# mcu.net
KiCad netlist of a schematic drawn in Altium Designer
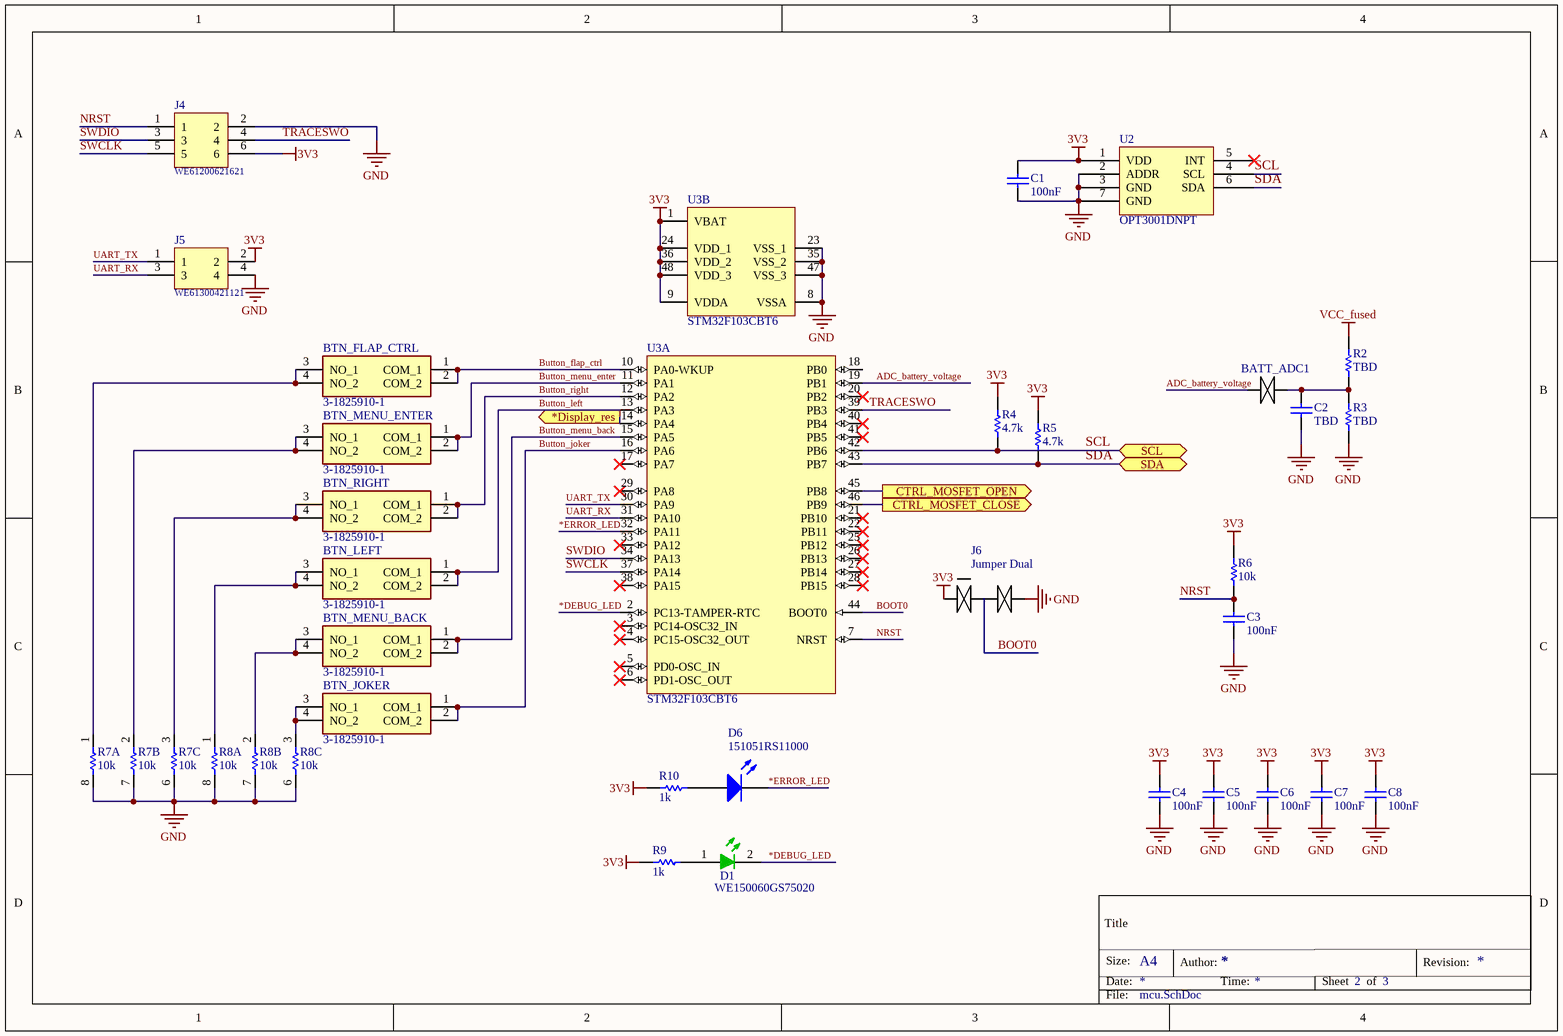
[diagram p0: mcu.SchDoc]

(export (version "E")
  (design (tool "Eeschema 10.0.6"))
  (components
    (comp (ref "BATT_ADC1")
      (value "TIMER")
      (footprint "JUMPER_SINGLE_SMALL")
      (description "2 pads which can be connected truth soldering")
      (libsource (lib "connectors") (part "JUMPER_SINGLE"))
    )
    (comp (ref "BTN_FLAP_CTRL")
      (value "3-1825910-1")
      (footprint "318259101")
      (description "Switch")
      (libsource (lib "Schlib") (part "3-1825910-1"))
    )
    (comp (ref "BTN_JOKER")
      (value "3-1825910-1")
      (footprint "318259101")
      (description "Switch")
      (libsource (lib "Schlib") (part "3-1825910-1"))
    )
    (comp (ref "BTN_LEFT")
      (value "3-1825910-1")
      (footprint "318259101")
      (description "Switch")
      (libsource (lib "Schlib") (part "3-1825910-1"))
    )
    (comp (ref "BTN_MENU_BACK")
      (value "3-1825910-1")
      (footprint "318259101")
      (description "Switch")
      (libsource (lib "Schlib") (part "3-1825910-1"))
    )
    (comp (ref "BTN_MENU_ENTER")
      (value "3-1825910-1")
      (footprint "318259101")
      (description "Switch")
      (libsource (lib "Schlib") (part "3-1825910-1"))
    )
    (comp (ref "BTN_RIGHT")
      (value "3-1825910-1")
      (footprint "318259101")
      (description "Switch")
      (libsource (lib "Schlib") (part "3-1825910-1"))
    )
    (comp (ref "C1")
      (value "100nF")
      (footprint "CAP0603")
      (description "Chip Capacitor 0603, Body 1.6x0.8mm, IPC Medium Density")
      (libsource (lib "capacitors") (part "Capacitor 0603"))
    )
    (comp (ref "C2")
      (value "TBD")
      (footprint "CAP0603")
      (description "Chip Capacitor 0603, Body 1.6x0.8mm, IPC Medium Density")
      (libsource (lib "capacitors") (part "Capacitor 0603"))
    )
    (comp (ref "C3")
      (value "100nF")
      (footprint "CAP0603")
      (description "Chip Capacitor 0603, Body 1.6x0.8mm, IPC Medium Density")
      (libsource (lib "capacitors") (part "Capacitor 0603"))
    )
    (comp (ref "C4")
      (value "100nF")
      (footprint "CAP0603")
      (description "Chip Capacitor 0603, Body 1.6x0.8mm, IPC Medium Density")
      (libsource (lib "capacitors") (part "Capacitor 0603"))
    )
    (comp (ref "C5")
      (value "100nF")
      (footprint "CAP0603")
      (description "Chip Capacitor 0603, Body 1.6x0.8mm, IPC Medium Density")
      (libsource (lib "capacitors") (part "Capacitor 0603"))
    )
    (comp (ref "C6")
      (value "100nF")
      (footprint "CAP0603")
      (description "Chip Capacitor 0603, Body 1.6x0.8mm, IPC Medium Density")
      (libsource (lib "capacitors") (part "Capacitor 0603"))
    )
    (comp (ref "C7")
      (value "100nF")
      (footprint "CAP0603")
      (description "Chip Capacitor 0603, Body 1.6x0.8mm, IPC Medium Density")
      (libsource (lib "capacitors") (part "Capacitor 0603"))
    )
    (comp (ref "C8")
      (value "100nF")
      (footprint "CAP0603")
      (description "Chip Capacitor 0603, Body 1.6x0.8mm, IPC Medium Density")
      (libsource (lib "capacitors") (part "Capacitor 0603"))
    )
    (comp (ref "D1")
      (value "WE150060GS75020")
      (footprint "0603 LED Green")
      (description "LED, SMT, 0603(1608), 1.1mm thickness, Green")
      (libsource (lib "diodes") (part "LED Green 0603"))
    )
    (comp (ref "D6")
      (value "151051RS11000")
      (footprint "Type 5mm")
      (description "THT LED round mono-color color lens, WL-TMRW, Red")
      (fields (field (name "MANUFACTURER") "Wuerth Elektronik"))
      (libsource (lib "Altium Content Vault") (part "WE-LED_K1A2-2"))
    )
    (comp (ref "J4")
      (value "WE61200621621")
      (footprint "WE61200621621")
      (description "WR-PHD Box Header, THT, pitch 2.54mm, Dual Row, Vertical, 6pin")
      (fields (field (name "PART NUMBER") "61300621121") (field (name "PUBLISHER") "Wurth Elektronik"))
      (libsource (lib "connectors") (part "WE61200621621"))
    )
    (comp (ref "J5")
      (value "WE61300421121")
      (footprint "WE61300421121")
      (description "WR-PHD Pin Header, THT, pitch 2.54mm, Dual Row, Vertical, 4pin")
      (fields (field (name "PART NUMBER") "61300421121") (field (name "PUBLISHER") "Wurth Elektronik"))
      (libsource (lib "connectors") (part "WE61300421121"))
    )
    (comp (ref "J6")
      (value "Jumper Dual")
      (footprint "Jumper Dual")
      (libsource (lib "miscellaneous") (part "Jumper Dual"))
    )
    (comp (ref "R2")
      (value "TBD")
      (footprint "RES0603")
      (description "Chip Resistor 0603, Body 1.6x0.8mm, IPC Medium Density")
      (libsource (lib "resistors") (part "Resistor 0603"))
    )
    (comp (ref "R3")
      (value "TBD")
      (footprint "RES0603")
      (description "Chip Resistor 0603, Body 1.6x0.8mm, IPC Medium Density")
      (libsource (lib "resistors") (part "Resistor 0603"))
    )
    (comp (ref "R4")
      (value "4.7k")
      (footprint "RES0603")
      (description "Chip Resistor 0603, Body 1.6x0.8mm, IPC Medium Density")
      (libsource (lib "resistors") (part "Resistor 0603"))
    )
    (comp (ref "R5")
      (value "4.7k")
      (footprint "RES0603")
      (description "Chip Resistor 0603, Body 1.6x0.8mm, IPC Medium Density")
      (libsource (lib "resistors") (part "Resistor 0603"))
    )
    (comp (ref "R6")
      (value "10k")
      (footprint "RES0603")
      (description "Chip Resistor 0603, Body 1.0x0.5mm, IPC Medium Density")
      (libsource (lib "resistors") (part "Resistor 0603"))
    )
    (comp (ref "R7")
      (value "10k")
      (footprint "BOUR-CAT16-103J4LF_M")
      (description "10k Array in Alternative symbol")
      (fields (field (name "Comment") "CAT16-103J4LF"))
      (libsource (lib "resistors") (part "CAT16-103J4LF alternative"))
    )
    (comp (ref "R8")
      (value "10k")
      (footprint "BOUR-CAT16-103J4LF_M")
      (description "10k Array in Alternative symbol")
      (fields (field (name "Comment") "CAT16-103J4LF"))
      (libsource (lib "resistors") (part "CAT16-103J4LF alternative"))
    )
    (comp (ref "R9")
      (value "1k")
      (footprint "RES0603")
      (description "Chip Resistor 0603, Body 1.6x0.8mm, IPC Medium Density")
      (libsource (lib "resistors") (part "Resistor 0603"))
    )
    (comp (ref "R10")
      (value "1k")
      (footprint "RES0603")
      (description "Chip Resistor 0603, Body 1.6x0.8mm, IPC Medium Density")
      (libsource (lib "resistors") (part "Resistor 0603"))
    )
    (comp (ref "U2")
      (value "OPT3001DNPT")
      (footprint "OPT3001DNPT")
      (description "Sensoren für Umgebungslicht Ambient Light Sensor -USON -40 to 85")
      (libsource (lib "ic_sensors") (part "OPT3001DNPT"))
    )
    (comp (ref "U3")
      (value "STM32F103CBT6")
      (footprint "STM-LQFP48_M")
      (fields (field (name "PARTNUMBER") "STM32F103C8T6"))
      (libsource (lib "ic_processors") (part "STM32F103CBT6"))
    )
  )
  (nets
    (net (code "1") (name "/*DEBUG_LED") (class "Default")
      (node (ref "D1") (pin "2") (pinfunction "K_2") (pintype "passive"))
      (node (ref "U3") (pin "2") (pinfunction "PC13-TAMPER-RTC_2") (pintype "bidirectional"))
    )
    (net (code "2") (name "/*Display_res") (class "Default")
      (node (ref "U3") (pin "14") (pinfunction "PA4_14") (pintype "bidirectional"))
    )
    (net (code "3") (name "/*ERROR_LED") (class "Default")
      (node (ref "D6") (pin "1") (pinfunction "K_1") (pintype "passive"))
      (node (ref "U3") (pin "32") (pinfunction "PA11_32") (pintype "bidirectional"))
    )
    (net (code "4") (name "/ADC_battery_voltage") (class "Default")
      (node (ref "BATT_ADC1") (pin "2") (pinfunction "B_2") (pintype "passive"))
      (node (ref "U3") (pin "19") (pinfunction "PB1_19") (pintype "bidirectional"))
    )
    (net (code "5") (name "/BOOT0") (class "Default")
      (node (ref "J6") (pin "3") (pinfunction "C_3") (pintype "passive"))
      (node (ref "U3") (pin "44") (pinfunction "BOOT0_44") (pintype "input"))
    )
    (net (code "6") (name "/Button_flap_ctrl") (class "Default")
      (node (ref "BTN_FLAP_CTRL") (pin "1") (pinfunction "COM_1_1") (pintype "passive"))
      (node (ref "BTN_FLAP_CTRL") (pin "2") (pinfunction "COM_2_2") (pintype "passive"))
      (node (ref "U3") (pin "10") (pinfunction "PA0-WKUP_10") (pintype "bidirectional"))
    )
    (net (code "7") (name "/Button_joker") (class "Default")
      (node (ref "BTN_JOKER") (pin "1") (pinfunction "COM_1_1") (pintype "passive"))
      (node (ref "BTN_JOKER") (pin "2") (pinfunction "COM_2_2") (pintype "passive"))
      (node (ref "U3") (pin "16") (pinfunction "PA6_16") (pintype "bidirectional"))
    )
    (net (code "8") (name "/Button_left") (class "Default")
      (node (ref "BTN_LEFT") (pin "1") (pinfunction "COM_1_1") (pintype "passive"))
      (node (ref "BTN_LEFT") (pin "2") (pinfunction "COM_2_2") (pintype "passive"))
      (node (ref "U3") (pin "13") (pinfunction "PA3_13") (pintype "bidirectional"))
    )
    (net (code "9") (name "/Button_menu_back") (class "Default")
      (node (ref "BTN_MENU_BACK") (pin "1") (pinfunction "COM_1_1") (pintype "passive"))
      (node (ref "BTN_MENU_BACK") (pin "2") (pinfunction "COM_2_2") (pintype "passive"))
      (node (ref "U3") (pin "15") (pinfunction "PA5_15") (pintype "bidirectional"))
    )
    (net (code "10") (name "/Button_menu_enter") (class "Default")
      (node (ref "BTN_MENU_ENTER") (pin "1") (pinfunction "COM_1_1") (pintype "passive"))
      (node (ref "BTN_MENU_ENTER") (pin "2") (pinfunction "COM_2_2") (pintype "passive"))
      (node (ref "U3") (pin "11") (pinfunction "PA1_11") (pintype "bidirectional"))
    )
    (net (code "11") (name "/Button_right") (class "Default")
      (node (ref "BTN_RIGHT") (pin "1") (pinfunction "COM_1_1") (pintype "passive"))
      (node (ref "BTN_RIGHT") (pin "2") (pinfunction "COM_2_2") (pintype "passive"))
      (node (ref "U3") (pin "12") (pinfunction "PA2_12") (pintype "bidirectional"))
    )
    (net (code "12") (name "/CTRL_MOSFET_CLOSE") (class "Default")
      (node (ref "U3") (pin "46") (pinfunction "PB9_46") (pintype "bidirectional"))
    )
    (net (code "13") (name "/CTRL_MOSFET_OPEN") (class "Default")
      (node (ref "U3") (pin "45") (pinfunction "PB8_45") (pintype "bidirectional"))
    )
    (net (code "14") (name "/NRST") (class "Default")
      (node (ref "C3") (pin "2") (pinfunction "2_2") (pintype "passive"))
      (node (ref "J4") (pin "1") (pinfunction "1_1") (pintype "power_in"))
      (node (ref "R6") (pin "1") (pinfunction "1_1") (pintype "passive"))
      (node (ref "U3") (pin "7") (pinfunction "NRST_7") (pintype "bidirectional"))
    )
    (net (code "15") (name "/SCL") (class "Default")
      (node (ref "R4") (pin "1") (pinfunction "1_1") (pintype "passive"))
      (node (ref "U2") (pin "4") (pinfunction "SCL_4") (pintype "passive"))
      (node (ref "U3") (pin "42") (pinfunction "PB6_42") (pintype "bidirectional"))
    )
    (net (code "16") (name "/SDA") (class "Default")
      (node (ref "R5") (pin "1") (pinfunction "1_1") (pintype "passive"))
      (node (ref "U2") (pin "6") (pinfunction "SDA_6") (pintype "passive"))
      (node (ref "U3") (pin "43") (pinfunction "PB7_43") (pintype "bidirectional"))
    )
    (net (code "17") (name "/SWCLK") (class "Default")
      (node (ref "J4") (pin "5") (pinfunction "5_5") (pintype "power_in"))
      (node (ref "U3") (pin "37") (pinfunction "PA14_37") (pintype "bidirectional"))
    )
    (net (code "18") (name "/SWDIO") (class "Default")
      (node (ref "J4") (pin "3") (pinfunction "3_3") (pintype "power_in"))
      (node (ref "U3") (pin "34") (pinfunction "PA13_34") (pintype "bidirectional"))
    )
    (net (code "19") (name "/TRACESWO") (class "Default")
      (node (ref "J4") (pin "4") (pinfunction "4_4") (pintype "power_in"))
      (node (ref "U3") (pin "39") (pinfunction "PB3_39") (pintype "bidirectional"))
    )
    (net (code "20") (name "/UART_RX") (class "Default")
      (node (ref "J5") (pin "3") (pinfunction "3_3") (pintype "power_in"))
      (node (ref "U3") (pin "31") (pinfunction "PA10_31") (pintype "bidirectional"))
    )
    (net (code "21") (name "/UART_TX") (class "Default")
      (node (ref "J5") (pin "1") (pinfunction "1_1") (pintype "power_in"))
      (node (ref "U3") (pin "30") (pinfunction "PA9_30") (pintype "bidirectional"))
    )
    (net (code "22") (name "3V3") (class "Default")
      (node (ref "C1") (pin "2") (pinfunction "2_2") (pintype "passive"))
      (node (ref "C4") (pin "2") (pinfunction "2_2") (pintype "passive"))
      (node (ref "C5") (pin "2") (pinfunction "2_2") (pintype "passive"))
      (node (ref "C6") (pin "2") (pinfunction "2_2") (pintype "passive"))
      (node (ref "C7") (pin "2") (pinfunction "2_2") (pintype "passive"))
      (node (ref "C8") (pin "2") (pinfunction "2_2") (pintype "passive"))
      (node (ref "J4") (pin "6") (pinfunction "6_6") (pintype "power_in"))
      (node (ref "J5") (pin "2") (pinfunction "2_2") (pintype "power_in"))
      (node (ref "J6") (pin "1") (pinfunction "A_1") (pintype "passive"))
      (node (ref "R10") (pin "2") (pinfunction "2_2") (pintype "passive"))
      (node (ref "R4") (pin "2") (pinfunction "2_2") (pintype "passive"))
      (node (ref "R5") (pin "2") (pinfunction "2_2") (pintype "passive"))
      (node (ref "R6") (pin "2") (pinfunction "2_2") (pintype "passive"))
      (node (ref "R9") (pin "2") (pinfunction "2_2") (pintype "passive"))
      (node (ref "U2") (pin "1") (pinfunction "VDD_1") (pintype "passive"))
      (node (ref "U3") (pin "1") (pinfunction "VBAT_1") (pintype "power_in"))
      (node (ref "U3") (pin "24") (pinfunction "VDD_1_24") (pintype "power_in"))
      (node (ref "U3") (pin "36") (pinfunction "VDD_2_36") (pintype "power_in"))
      (node (ref "U3") (pin "48") (pinfunction "VDD_3_48") (pintype "power_in"))
      (node (ref "U3") (pin "9") (pinfunction "VDDA_9") (pintype "power_in"))
    )
    (net (code "23") (name "GND") (class "Default")
      (node (ref "C1") (pin "1") (pinfunction "1_1") (pintype "passive"))
      (node (ref "C2") (pin "1") (pinfunction "1_1") (pintype "passive"))
      (node (ref "C3") (pin "1") (pinfunction "1_1") (pintype "passive"))
      (node (ref "C4") (pin "1") (pinfunction "1_1") (pintype "passive"))
      (node (ref "C5") (pin "1") (pinfunction "1_1") (pintype "passive"))
      (node (ref "C6") (pin "1") (pinfunction "1_1") (pintype "passive"))
      (node (ref "C7") (pin "1") (pinfunction "1_1") (pintype "passive"))
      (node (ref "C8") (pin "1") (pinfunction "1_1") (pintype "passive"))
      (node (ref "J4") (pin "2") (pinfunction "2_2") (pintype "power_in"))
      (node (ref "J5") (pin "4") (pinfunction "4_4") (pintype "power_in"))
      (node (ref "J6") (pin "2") (pinfunction "B_2") (pintype "passive"))
      (node (ref "R3") (pin "1") (pinfunction "1_1") (pintype "passive"))
      (node (ref "R7") (pin "6") (pinfunction "2_6") (pintype "passive"))
      (node (ref "R7") (pin "7") (pinfunction "2_7") (pintype "passive"))
      (node (ref "R7") (pin "8") (pinfunction "2_8") (pintype "passive"))
      (node (ref "R8") (pin "6") (pinfunction "2_6") (pintype "passive"))
      (node (ref "R8") (pin "7") (pinfunction "2_7") (pintype "passive"))
      (node (ref "R8") (pin "8") (pinfunction "2_8") (pintype "passive"))
      (node (ref "U2") (pin "2") (pinfunction "ADDR_2") (pintype "passive"))
      (node (ref "U2") (pin "3") (pinfunction "GND_3") (pintype "passive"))
      (node (ref "U2") (pin "7") (pinfunction "GND_7") (pintype "passive"))
      (node (ref "U3") (pin "23") (pinfunction "VSS_1_23") (pintype "power_in"))
      (node (ref "U3") (pin "35") (pinfunction "VSS_2_35") (pintype "power_in"))
      (node (ref "U3") (pin "47") (pinfunction "VSS_3_47") (pintype "power_in"))
      (node (ref "U3") (pin "8") (pinfunction "VSSA_8") (pintype "power_in"))
    )
    (net (code "24") (name "Net-(BATT_ADC1-A)") (class "Default")
      (node (ref "BATT_ADC1") (pin "1") (pinfunction "A_1") (pintype "passive"))
      (node (ref "C2") (pin "2") (pinfunction "2_2") (pintype "passive"))
      (node (ref "R2") (pin "1") (pinfunction "1_1") (pintype "passive"))
      (node (ref "R3") (pin "2") (pinfunction "2_2") (pintype "passive"))
    )
    (net (code "25") (name "Net-(BTN_FLAP_CTRL-NO_1)") (class "Default")
      (node (ref "BTN_FLAP_CTRL") (pin "3") (pinfunction "NO_1_3") (pintype "passive"))
      (node (ref "BTN_FLAP_CTRL") (pin "4") (pinfunction "NO_2_4") (pintype "passive"))
      (node (ref "R7") (pin "1") (pinfunction "1_1") (pintype "passive"))
    )
    (net (code "26") (name "Net-(BTN_JOKER-NO_1)") (class "Default")
      (node (ref "BTN_JOKER") (pin "3") (pinfunction "NO_1_3") (pintype "passive"))
      (node (ref "BTN_JOKER") (pin "4") (pinfunction "NO_2_4") (pintype "passive"))
      (node (ref "R8") (pin "3") (pinfunction "1_3") (pintype "passive"))
    )
    (net (code "27") (name "Net-(BTN_LEFT-NO_1)") (class "Default")
      (node (ref "BTN_LEFT") (pin "3") (pinfunction "NO_1_3") (pintype "passive"))
      (node (ref "BTN_LEFT") (pin "4") (pinfunction "NO_2_4") (pintype "passive"))
      (node (ref "R8") (pin "1") (pinfunction "1_1") (pintype "passive"))
    )
    (net (code "28") (name "Net-(BTN_MENU_BACK-NO_1)") (class "Default")
      (node (ref "BTN_MENU_BACK") (pin "3") (pinfunction "NO_1_3") (pintype "passive"))
      (node (ref "BTN_MENU_BACK") (pin "4") (pinfunction "NO_2_4") (pintype "passive"))
      (node (ref "R8") (pin "2") (pinfunction "1_2") (pintype "passive"))
    )
    (net (code "29") (name "Net-(BTN_MENU_ENTER-NO_1)") (class "Default")
      (node (ref "BTN_MENU_ENTER") (pin "3") (pinfunction "NO_1_3") (pintype "passive"))
      (node (ref "BTN_MENU_ENTER") (pin "4") (pinfunction "NO_2_4") (pintype "passive"))
      (node (ref "R7") (pin "2") (pinfunction "1_2") (pintype "passive"))
    )
    (net (code "30") (name "Net-(BTN_RIGHT-NO_1)") (class "Default")
      (node (ref "BTN_RIGHT") (pin "3") (pinfunction "NO_1_3") (pintype "passive"))
      (node (ref "BTN_RIGHT") (pin "4") (pinfunction "NO_2_4") (pintype "passive"))
      (node (ref "R7") (pin "3") (pinfunction "1_3") (pintype "passive"))
    )
    (net (code "31") (name "Net-(D1-A)") (class "Default")
      (node (ref "D1") (pin "1") (pinfunction "A_1") (pintype "passive"))
      (node (ref "R9") (pin "1") (pinfunction "1_1") (pintype "passive"))
    )
    (net (code "32") (name "Net-(D6-A)") (class "Default")
      (node (ref "D6") (pin "2") (pinfunction "A_2") (pintype "passive"))
      (node (ref "R10") (pin "1") (pinfunction "1_1") (pintype "passive"))
    )
    (net (code "33") (name "VCC_fused") (class "Default")
      (node (ref "R2") (pin "2") (pinfunction "2_2") (pintype "passive"))
    )
    (net (code "34") (name "unconnected-(U2-INT-Pad5)") (class "Default")
      (node (ref "U2") (pin "5") (pinfunction "INT_5") (pintype "passive+no_connect"))
    )
    (net (code "35") (name "unconnected-(U3A-PA7-Pad17)") (class "Default")
      (node (ref "U3") (pin "17") (pinfunction "PA7_17") (pintype "bidirectional+no_connect"))
    )
    (net (code "36") (name "unconnected-(U3A-PA8-Pad29)") (class "Default")
      (node (ref "U3") (pin "29") (pinfunction "PA8_29") (pintype "bidirectional+no_connect"))
    )
    (net (code "37") (name "unconnected-(U3A-PA12-Pad33)") (class "Default")
      (node (ref "U3") (pin "33") (pinfunction "PA12_33") (pintype "bidirectional+no_connect"))
    )
    (net (code "38") (name "unconnected-(U3A-PA15-Pad38)") (class "Default")
      (node (ref "U3") (pin "38") (pinfunction "PA15_38") (pintype "bidirectional+no_connect"))
    )
    (net (code "39") (name "unconnected-(U3A-PB0-Pad18)") (class "Default")
      (node (ref "U3") (pin "18") (pinfunction "PB0_18") (pintype "bidirectional"))
    )
    (net (code "40") (name "unconnected-(U3A-PB2-Pad20)") (class "Default")
      (node (ref "U3") (pin "20") (pinfunction "PB2_20") (pintype "bidirectional+no_connect"))
    )
    (net (code "41") (name "unconnected-(U3A-PB4-Pad40)") (class "Default")
      (node (ref "U3") (pin "40") (pinfunction "PB4_40") (pintype "bidirectional+no_connect"))
    )
    (net (code "42") (name "unconnected-(U3A-PB5-Pad41)") (class "Default")
      (node (ref "U3") (pin "41") (pinfunction "PB5_41") (pintype "bidirectional+no_connect"))
    )
    (net (code "43") (name "unconnected-(U3A-PB10-Pad21)") (class "Default")
      (node (ref "U3") (pin "21") (pinfunction "PB10_21") (pintype "bidirectional+no_connect"))
    )
    (net (code "44") (name "unconnected-(U3A-PB11-Pad22)") (class "Default")
      (node (ref "U3") (pin "22") (pinfunction "PB11_22") (pintype "bidirectional+no_connect"))
    )
    (net (code "45") (name "unconnected-(U3A-PB12-Pad25)") (class "Default")
      (node (ref "U3") (pin "25") (pinfunction "PB12_25") (pintype "bidirectional+no_connect"))
    )
    (net (code "46") (name "unconnected-(U3A-PB13-Pad26)") (class "Default")
      (node (ref "U3") (pin "26") (pinfunction "PB13_26") (pintype "bidirectional+no_connect"))
    )
    (net (code "47") (name "unconnected-(U3A-PB14-Pad27)") (class "Default")
      (node (ref "U3") (pin "27") (pinfunction "PB14_27") (pintype "bidirectional+no_connect"))
    )
    (net (code "48") (name "unconnected-(U3A-PB15-Pad28)") (class "Default")
      (node (ref "U3") (pin "28") (pinfunction "PB15_28") (pintype "bidirectional+no_connect"))
    )
    (net (code "49") (name "unconnected-(U3A-PC14-OSC32_IN-Pad3)") (class "Default")
      (node (ref "U3") (pin "3") (pinfunction "PC14-OSC32_IN_3") (pintype "bidirectional+no_connect"))
    )
    (net (code "50") (name "unconnected-(U3A-PC15-OSC32_OUT-Pad4)") (class "Default")
      (node (ref "U3") (pin "4") (pinfunction "PC15-OSC32_OUT_4") (pintype "bidirectional+no_connect"))
    )
    (net (code "51") (name "unconnected-(U3A-PD0-OSC_IN-Pad5)") (class "Default")
      (node (ref "U3") (pin "5") (pinfunction "PD0-OSC_IN_5") (pintype "bidirectional+no_connect"))
    )
    (net (code "52") (name "unconnected-(U3A-PD1-OSC_OUT-Pad6)") (class "Default")
      (node (ref "U3") (pin "6") (pinfunction "PD1-OSC_OUT_6") (pintype "bidirectional+no_connect"))
    )
  )
)
